# V2.net
KiCad netlist of a schematic drawn in EAGLE
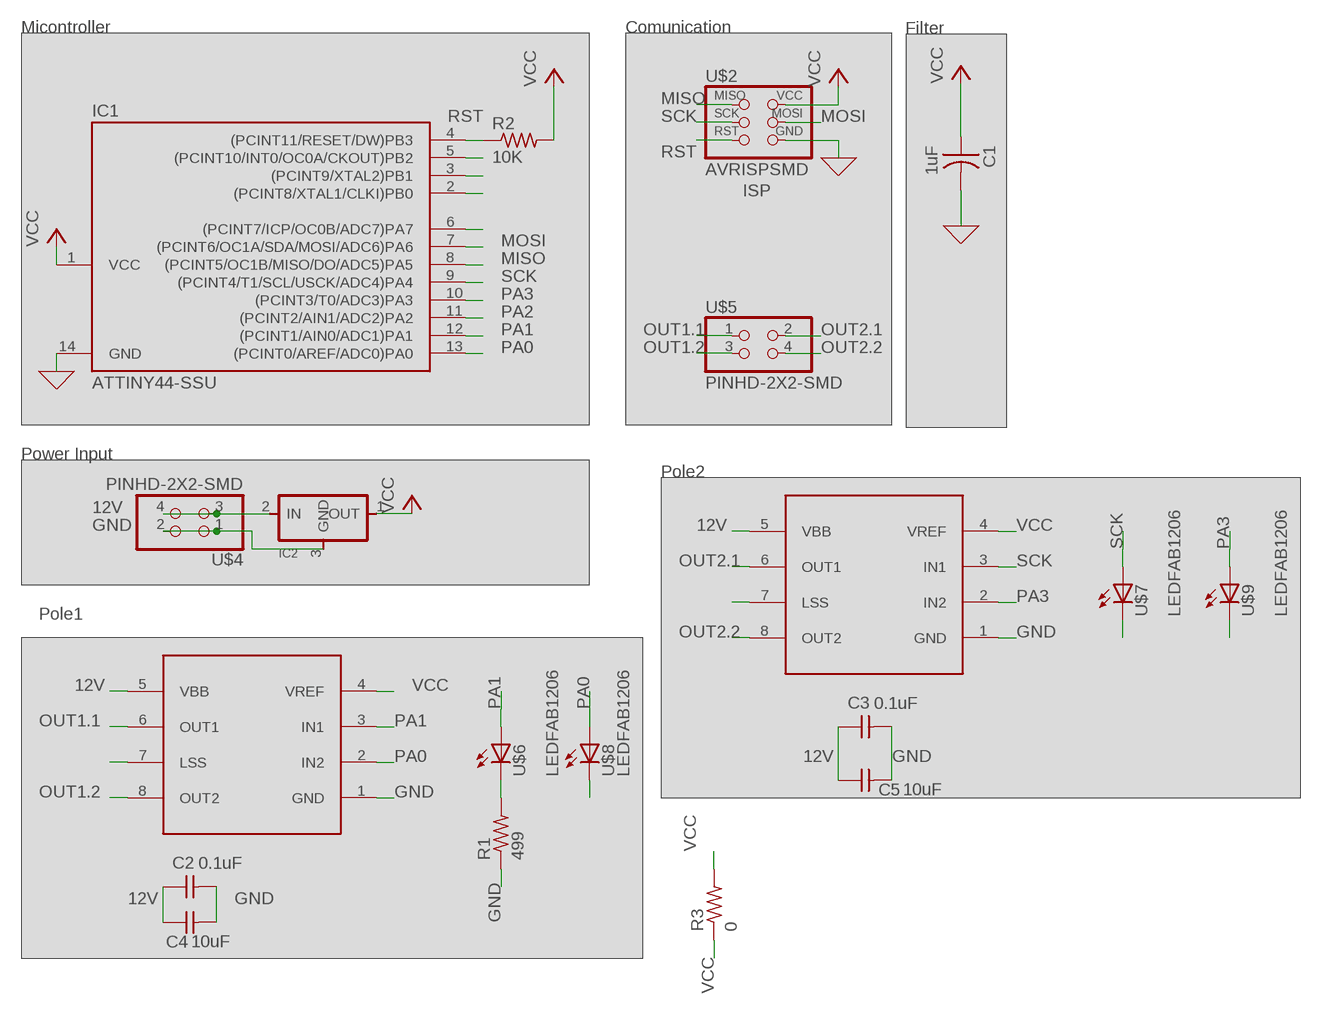
[diagram p0: schematic, sheet 1]

(export (version "E")
  (design (tool "Eeschema 10.0.6"))
  (components
    (comp (ref "C1")
      (value "1uF")
      (footprint "eagle-import:C1206FAB")
      (libsource (lib "eagle-import") (part "CAP-US1206FAB"))
    )
    (comp (ref "C2")
      (value "0.1uF")
      (footprint "eagle-import:C1206FAB")
      (libsource (lib "eagle-import") (part "CAP-UNPOLARIZEDFAB"))
    )
    (comp (ref "C3")
      (value "0.1uF")
      (footprint "eagle-import:C1206FAB")
      (libsource (lib "eagle-import") (part "CAP-UNPOLARIZEDFAB"))
    )
    (comp (ref "C4")
      (value "10uF")
      (footprint "eagle-import:C1206FAB")
      (libsource (lib "eagle-import") (part "CAP-UNPOLARIZEDFAB"))
    )
    (comp (ref "C5")
      (value "10uF")
      (footprint "eagle-import:C1206FAB")
      (libsource (lib "eagle-import") (part "CAP-UNPOLARIZEDFAB"))
    )
    (comp (ref "IC1")
      (value "ATTINY44-SSU")
      (footprint "eagle-import:SOIC14")
      (libsource (lib "eagle-import") (part "ATTINY44-SSU"))
    )
    (comp (ref "IC2")
      (value "REGULATORSOT23")
      (footprint "eagle-import:SOT23")
      (libsource (lib "eagle-import") (part "REGULATORSOT23"))
    )
    (comp (ref "R1")
      (value "499")
      (footprint "eagle-import:R1206FAB")
      (libsource (lib "eagle-import") (part "RES-US1206FAB"))
    )
    (comp (ref "R2")
      (value "10K")
      (footprint "eagle-import:R1206FAB")
      (libsource (lib "eagle-import") (part "RES-US1206FAB"))
    )
    (comp (ref "R3")
      (value "0")
      (footprint "eagle-import:R1206FAB")
      (libsource (lib "eagle-import") (part "RES-US1206FAB"))
    )
    (comp (ref "U$1")
      (value "A4953-H-BRIDGE-MOTOR-DRIVER")
      (footprint "eagle-import:SOIC8")
      (libsource (lib "eagle-import") (part "A4953-H-BRIDGE-MOTOR-DRIVER"))
    )
    (comp (ref "U$2")
      (value "AVRISPSMD")
      (footprint "eagle-import:2X03SMD")
      (libsource (lib "eagle-import") (part "AVRISPSMD"))
    )
    (comp (ref "U$3")
      (value "A4953-H-BRIDGE-MOTOR-DRIVER")
      (footprint "eagle-import:SOIC8")
      (libsource (lib "eagle-import") (part "A4953-H-BRIDGE-MOTOR-DRIVER"))
    )
    (comp (ref "U$4")
      (value "PINHD-2X2-SMD")
      (footprint "eagle-import:2X02SMD")
      (libsource (lib "eagle-import") (part "PINHD-2X2-SMD"))
    )
    (comp (ref "U$5")
      (value "PINHD-2X2-SMD")
      (footprint "eagle-import:2X02SMD")
      (libsource (lib "eagle-import") (part "PINHD-2X2-SMD"))
    )
    (comp (ref "U$6")
      (value "LEDFAB1206")
      (footprint "eagle-import:LED1206FAB")
      (libsource (lib "eagle-import") (part "LEDFAB1206"))
    )
    (comp (ref "U$7")
      (value "LEDFAB1206")
      (footprint "eagle-import:LED1206FAB")
      (libsource (lib "eagle-import") (part "LEDFAB1206"))
    )
    (comp (ref "U$8")
      (value "LEDFAB1206")
      (footprint "eagle-import:LED1206FAB")
      (libsource (lib "eagle-import") (part "LEDFAB1206"))
    )
    (comp (ref "U$9")
      (value "LEDFAB1206")
      (footprint "eagle-import:LED1206FAB")
      (libsource (lib "eagle-import") (part "LEDFAB1206"))
    )
  )
  (nets
    (net (code "1") (name "/12V") (class "Default")
      (node (ref "C2") (pin "1") (pinfunction "1_1") (pintype "passive"))
      (node (ref "C3") (pin "1") (pinfunction "1_1") (pintype "passive"))
      (node (ref "C4") (pin "1") (pinfunction "1_1") (pintype "passive"))
      (node (ref "C5") (pin "1") (pinfunction "1_1") (pintype "passive"))
      (node (ref "IC2") (pin "2") (pinfunction "IN_2") (pintype "bidirectional"))
      (node (ref "U$1") (pin "5") (pinfunction "VBB_5") (pintype "bidirectional"))
      (node (ref "U$3") (pin "5") (pinfunction "VBB_5") (pintype "bidirectional"))
      (node (ref "U$4") (pin "3") (pinfunction "3_3") (pintype "passive"))
      (node (ref "U$4") (pin "4") (pinfunction "4_4") (pintype "passive"))
    )
    (net (code "2") (name "/MISO") (class "Default")
      (node (ref "IC1") (pin "6") (pinfunction "(PCINT7/ICP/OC0B/ADC7)PA7_6") (pintype "bidirectional"))
      (node (ref "IC1") (pin "8") (pinfunction "(PCINT5/OC1B/MISO/DO/ADC5)PA5_8") (pintype "bidirectional"))
      (node (ref "U$2") (pin "1") (pinfunction "MISO_1") (pintype "passive"))
    )
    (net (code "3") (name "/MOSI") (class "Default")
      (node (ref "IC1") (pin "7") (pinfunction "(PCINT6/OC1A/SDA/MOSI/ADC6)PA6_7") (pintype "bidirectional"))
      (node (ref "U$2") (pin "4") (pinfunction "MOSI_4") (pintype "passive"))
    )
    (net (code "4") (name "/OUT1.1") (class "Default")
      (node (ref "U$1") (pin "6") (pinfunction "OUT1_6") (pintype "bidirectional"))
      (node (ref "U$5") (pin "1") (pinfunction "1_1") (pintype "passive"))
    )
    (net (code "5") (name "/OUT1.2") (class "Default")
      (node (ref "U$1") (pin "8") (pinfunction "OUT2_8") (pintype "bidirectional"))
      (node (ref "U$5") (pin "3") (pinfunction "3_3") (pintype "passive"))
    )
    (net (code "6") (name "/OUT2.1") (class "Default")
      (node (ref "U$3") (pin "6") (pinfunction "OUT1_6") (pintype "bidirectional"))
      (node (ref "U$5") (pin "2") (pinfunction "2_2") (pintype "passive"))
    )
    (net (code "7") (name "/OUT2.2") (class "Default")
      (node (ref "U$3") (pin "8") (pinfunction "OUT2_8") (pintype "bidirectional"))
      (node (ref "U$5") (pin "4") (pinfunction "4_4") (pintype "passive"))
    )
    (net (code "8") (name "/PA0") (class "Default")
      (node (ref "IC1") (pin "13") (pinfunction "(PCINT0/AREF/ADC0)PA0_13") (pintype "bidirectional"))
      (node (ref "U$1") (pin "2") (pinfunction "IN2_2") (pintype "bidirectional"))
      (node (ref "U$8") (pin "1") (pinfunction "A_1") (pintype "passive"))
    )
    (net (code "9") (name "/PA1") (class "Default")
      (node (ref "IC1") (pin "12") (pinfunction "(PCINT1/AIN0/ADC1)PA1_12") (pintype "bidirectional"))
      (node (ref "U$1") (pin "3") (pinfunction "IN1_3") (pintype "bidirectional"))
      (node (ref "U$6") (pin "1") (pinfunction "A_1") (pintype "passive"))
    )
    (net (code "10") (name "/PA2") (class "Default")
      (node (ref "IC1") (pin "11") (pinfunction "(PCINT2/AIN1/ADC2)PA2_11") (pintype "bidirectional"))
    )
    (net (code "11") (name "/PA3") (class "Default")
      (node (ref "IC1") (pin "10") (pinfunction "(PCINT3/T0/ADC3)PA3_10") (pintype "bidirectional"))
      (node (ref "U$3") (pin "2") (pinfunction "IN2_2") (pintype "bidirectional"))
      (node (ref "U$9") (pin "1") (pinfunction "A_1") (pintype "passive"))
    )
    (net (code "12") (name "/RES") (class "Default")
      (node (ref "R1") (pin "2") (pinfunction "2_2") (pintype "passive"))
      (node (ref "U$6") (pin "2") (pinfunction "C_2") (pintype "passive"))
      (node (ref "U$7") (pin "2") (pinfunction "C_2") (pintype "passive"))
      (node (ref "U$8") (pin "2") (pinfunction "C_2") (pintype "passive"))
      (node (ref "U$9") (pin "2") (pinfunction "C_2") (pintype "passive"))
    )
    (net (code "13") (name "/RST") (class "Default")
      (node (ref "IC1") (pin "4") (pinfunction "(PCINT11/RESET/DW)PB3_4") (pintype "bidirectional"))
      (node (ref "R2") (pin "1") (pinfunction "1_1") (pintype "passive"))
      (node (ref "U$2") (pin "5") (pinfunction "RST_5") (pintype "passive"))
    )
    (net (code "14") (name "/SCK") (class "Default")
      (node (ref "IC1") (pin "9") (pinfunction "(PCINT4/T1/SCL/USCK/ADC4)PA4_9") (pintype "bidirectional"))
      (node (ref "U$2") (pin "3") (pinfunction "SCK_3") (pintype "passive"))
      (node (ref "U$3") (pin "3") (pinfunction "IN1_3") (pintype "bidirectional"))
      (node (ref "U$7") (pin "1") (pinfunction "A_1") (pintype "passive"))
    )
    (net (code "15") (name "GND") (class "Default")
      (node (ref "C1") (pin "2") (pinfunction "2_2") (pintype "passive"))
      (node (ref "C2") (pin "2") (pinfunction "2_2") (pintype "passive"))
      (node (ref "C3") (pin "2") (pinfunction "2_2") (pintype "passive"))
      (node (ref "C4") (pin "2") (pinfunction "2_2") (pintype "passive"))
      (node (ref "C5") (pin "2") (pinfunction "2_2") (pintype "passive"))
      (node (ref "IC1") (pin "14") (pinfunction "GND_14") (pintype "power_in"))
      (node (ref "IC2") (pin "3") (pinfunction "GND_3") (pintype "bidirectional"))
      (node (ref "R1") (pin "1") (pinfunction "1_1") (pintype "passive"))
      (node (ref "U$1") (pin "1") (pinfunction "GND_1") (pintype "bidirectional"))
      (node (ref "U$2") (pin "6") (pinfunction "GND_6") (pintype "passive"))
      (node (ref "U$3") (pin "1") (pinfunction "GND_1") (pintype "bidirectional"))
      (node (ref "U$4") (pin "1") (pinfunction "1_1") (pintype "passive"))
      (node (ref "U$4") (pin "2") (pinfunction "2_2") (pintype "passive"))
    )
    (net (code "16") (name "VCC") (class "Default")
      (node (ref "C1") (pin "1") (pinfunction "1_1") (pintype "passive"))
      (node (ref "IC1") (pin "1") (pinfunction "VCC_1") (pintype "power_in"))
      (node (ref "IC2") (pin "1") (pinfunction "OUT_1") (pintype "bidirectional"))
      (node (ref "R2") (pin "2") (pinfunction "2_2") (pintype "passive"))
      (node (ref "R3") (pin "1") (pinfunction "1_1") (pintype "passive"))
      (node (ref "R3") (pin "2") (pinfunction "2_2") (pintype "passive"))
      (node (ref "U$1") (pin "4") (pinfunction "VREF_4") (pintype "bidirectional"))
      (node (ref "U$2") (pin "2") (pinfunction "VCC_2") (pintype "passive"))
      (node (ref "U$3") (pin "4") (pinfunction "VREF_4") (pintype "bidirectional"))
    )
    (net (code "17") (name "unconnected-(IC1-(PCINT8{slash}XTAL1{slash}CLKI)PB0-Pad2)") (class "Default")
      (node (ref "IC1") (pin "2") (pinfunction "(PCINT8/XTAL1/CLKI)PB0_2") (pintype "bidirectional"))
    )
    (net (code "18") (name "unconnected-(IC1-(PCINT9{slash}XTAL2)PB1-Pad3)") (class "Default")
      (node (ref "IC1") (pin "3") (pinfunction "(PCINT9/XTAL2)PB1_3") (pintype "bidirectional"))
    )
    (net (code "19") (name "unconnected-(IC1-(PCINT10{slash}INT0{slash}OC0A{slash}CKOUT)PB2-Pad5)") (class "Default")
      (node (ref "IC1") (pin "5") (pinfunction "(PCINT10/INT0/OC0A/CKOUT)PB2_5") (pintype "bidirectional"))
    )
    (net (code "20") (name "unconnected-(U$1-LSS-Pad7)") (class "Default")
      (node (ref "U$1") (pin "7") (pinfunction "LSS_7") (pintype "bidirectional"))
    )
    (net (code "21") (name "unconnected-(U$3-LSS-Pad7)") (class "Default")
      (node (ref "U$3") (pin "7") (pinfunction "LSS_7") (pintype "bidirectional"))
    )
  )
)
